# nisetoro_wsc_adapter_v2.net
KiCad netlist of a schematic drawn in EAGLE
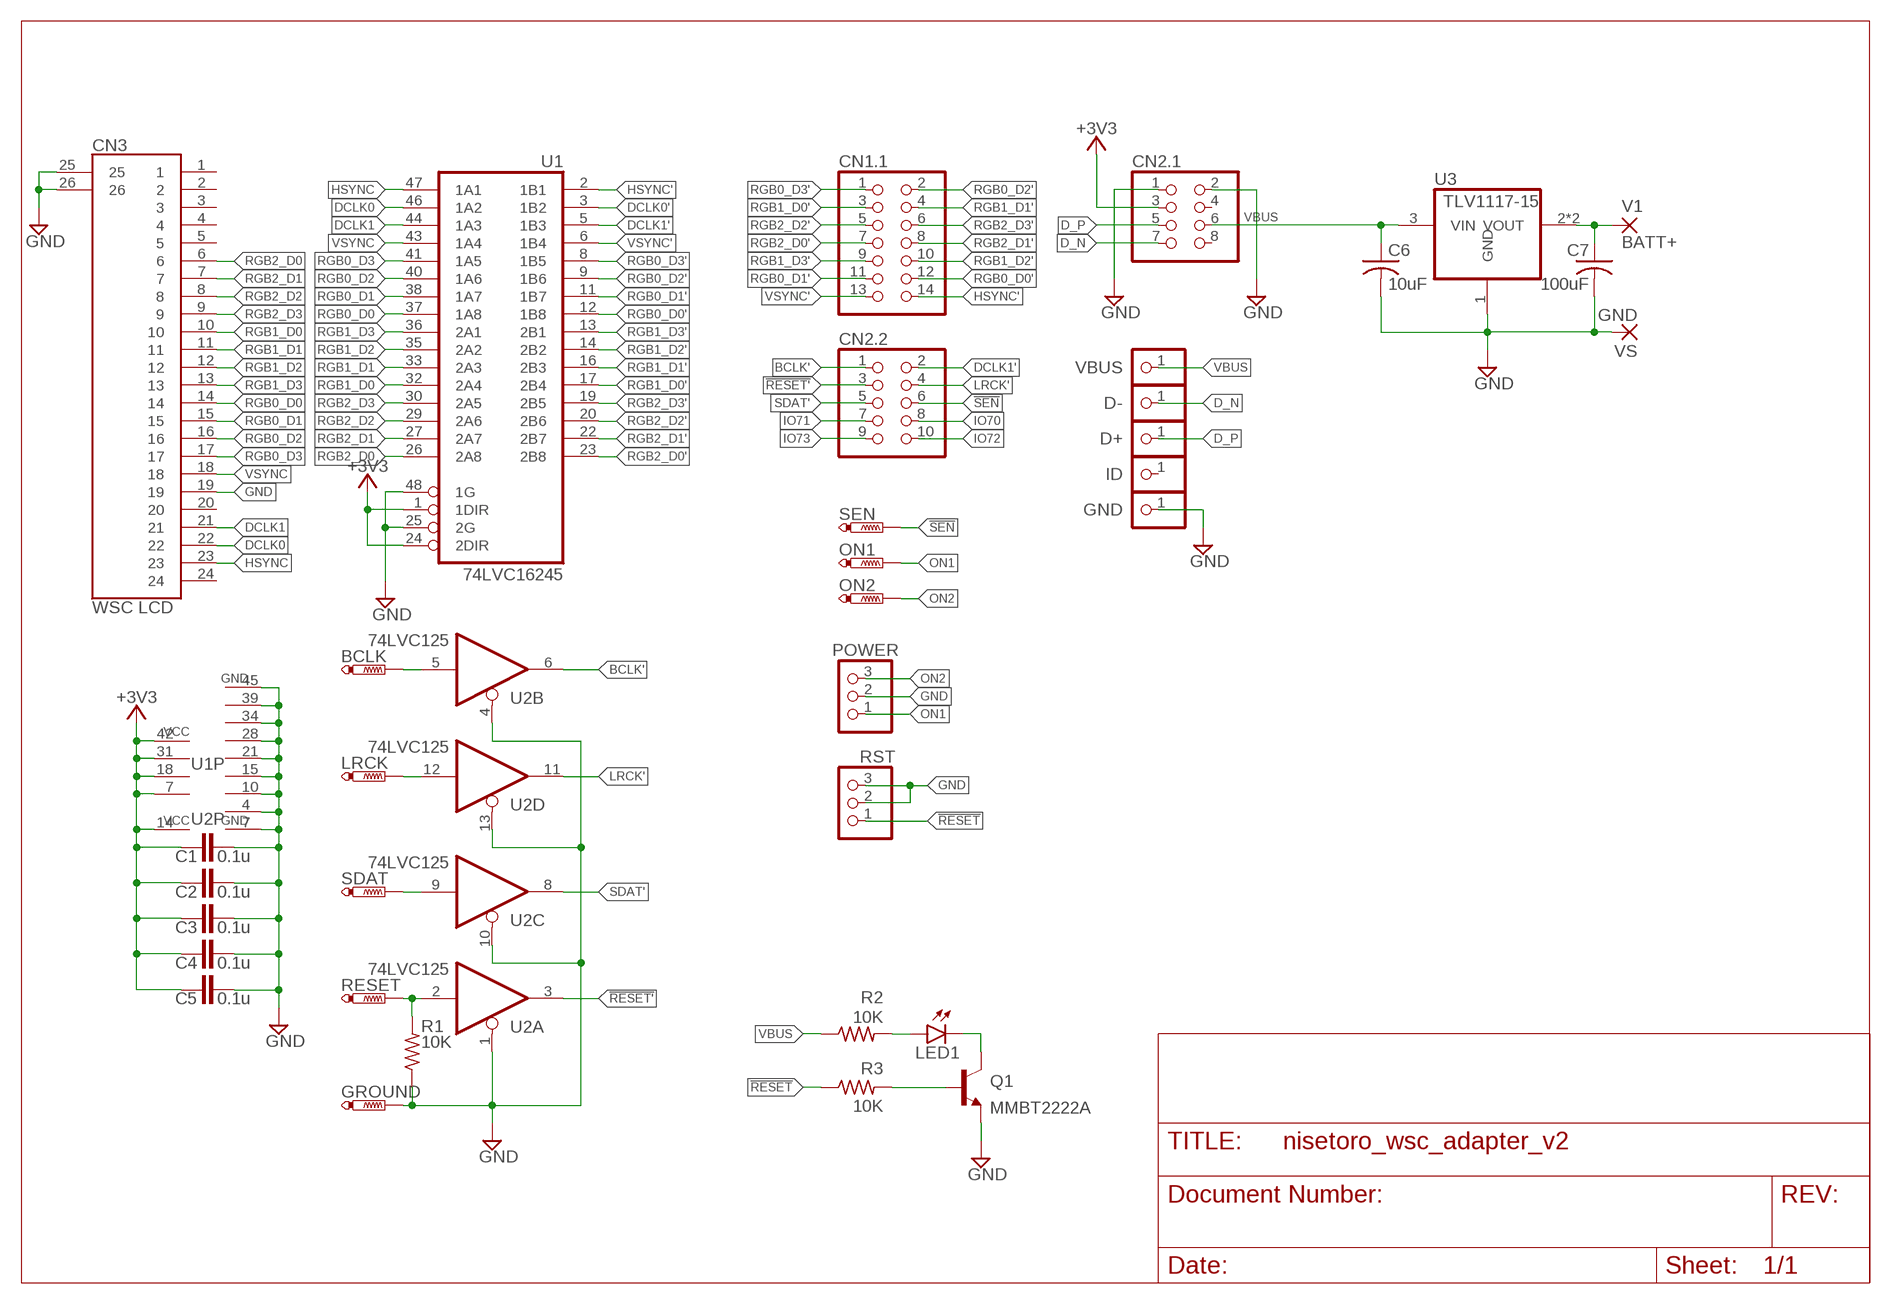
[diagram p0: schematic, sheet 1]

(export (version "E")
  (design (tool "Eeschema 10.0.6"))
  (components
    (comp (ref "BCLK")
      (value "PTR1B1,27")
      (footprint "eagle-import:B1,27")
      (libsource (lib "eagle-import") (part "PTR1B1,27"))
    )
    (comp (ref "C1")
      (value "0.1u")
      (footprint "eagle-import:C0603")
      (libsource (lib "eagle-import") (part "C-EUC0603"))
    )
    (comp (ref "C2")
      (value "0.1u")
      (footprint "eagle-import:C0603")
      (libsource (lib "eagle-import") (part "C-EUC0603"))
    )
    (comp (ref "C3")
      (value "0.1u")
      (footprint "eagle-import:C0603")
      (libsource (lib "eagle-import") (part "C-EUC0603"))
    )
    (comp (ref "C4")
      (value "0.1u")
      (footprint "eagle-import:C0603")
      (libsource (lib "eagle-import") (part "C-EUC0603"))
    )
    (comp (ref "C5")
      (value "0.1u")
      (footprint "eagle-import:C0603")
      (libsource (lib "eagle-import") (part "C-EUC0603"))
    )
    (comp (ref "C6")
      (value "10uF")
      (footprint "eagle-import:C1210")
      (libsource (lib "eagle-import") (part "C-USC1210"))
    )
    (comp (ref "C7")
      (value "100uF")
      (footprint "eagle-import:C1210")
      (libsource (lib "eagle-import") (part "C-USC1210"))
    )
    (comp (ref "CN1.1")
      (value "PINHD-2X7")
      (footprint "eagle-import:2X07")
      (libsource (lib "eagle-import") (part "PINHD-2X7"))
    )
    (comp (ref "CN2.1")
      (value "PINHD-2X4")
      (footprint "eagle-import:2X04")
      (libsource (lib "eagle-import") (part "PINHD-2X4"))
    )
    (comp (ref "CN2.2")
      (value "PINHD-2X5")
      (footprint "eagle-import:2X05")
      (libsource (lib "eagle-import") (part "PINHD-2X5"))
    )
    (comp (ref "CN3")
      (value "WSC LCD")
      (footprint "eagle-import:68712414022_R")
      (libsource (lib "eagle-import") (part "68712414022/R"))
    )
    (comp (ref "D+")
      (value "PINHD-1X1")
      (footprint "eagle-import:1X01")
      (libsource (lib "eagle-import") (part "PINHD-1X1"))
    )
    (comp (ref "D-")
      (value "PINHD-1X1")
      (footprint "eagle-import:1X01")
      (libsource (lib "eagle-import") (part "PINHD-1X1"))
    )
    (comp (ref "GND")
      (value "PINHD-1X1")
      (footprint "eagle-import:1X01")
      (libsource (lib "eagle-import") (part "PINHD-1X1"))
    )
    (comp (ref "GROUND")
      (value "PTR1B1,27")
      (footprint "eagle-import:B1,27")
      (libsource (lib "eagle-import") (part "PTR1B1,27"))
    )
    (comp (ref "ID")
      (value "PINHD-1X1")
      (footprint "eagle-import:1X01")
      (libsource (lib "eagle-import") (part "PINHD-1X1"))
    )
    (comp (ref "LED1")
      (value "LEDSML0603")
      (footprint "eagle-import:SML0603")
      (libsource (lib "eagle-import") (part "LEDSML0603"))
    )
    (comp (ref "LRCK")
      (value "PTR1B1,27")
      (footprint "eagle-import:B1,27")
      (libsource (lib "eagle-import") (part "PTR1B1,27"))
    )
    (comp (ref "ON1")
      (value "PTR1B1,27")
      (footprint "eagle-import:B1,27")
      (libsource (lib "eagle-import") (part "PTR1B1,27"))
    )
    (comp (ref "ON2")
      (value "PTR1B1,27")
      (footprint "eagle-import:B1,27")
      (libsource (lib "eagle-import") (part "PTR1B1,27"))
    )
    (comp (ref "POWER")
      (value "PINHD-1X3/ROUND")
      (footprint "eagle-import:1X03_ROUND")
      (libsource (lib "eagle-import") (part "PINHD-1X3/ROUND"))
    )
    (comp (ref "Q1")
      (value "MMBT2222A")
      (footprint "eagle-import:SOT23-BEC")
      (libsource (lib "eagle-import") (part "2N2222SOT23"))
    )
    (comp (ref "R1")
      (value "10K")
      (footprint "eagle-import:R0603")
      (libsource (lib "eagle-import") (part "R-US_R0603"))
    )
    (comp (ref "R2")
      (value "10K")
      (footprint "eagle-import:R0603")
      (libsource (lib "eagle-import") (part "R-US_R0603"))
    )
    (comp (ref "R3")
      (value "10K")
      (footprint "eagle-import:R0603")
      (libsource (lib "eagle-import") (part "R-US_R0603"))
    )
    (comp (ref "RESET")
      (value "PTR1B1,27")
      (footprint "eagle-import:B1,27")
      (libsource (lib "eagle-import") (part "PTR1B1,27"))
    )
    (comp (ref "RST")
      (value "PINHD-1X3/ROUND")
      (footprint "eagle-import:1X03_ROUND")
      (libsource (lib "eagle-import") (part "PINHD-1X3/ROUND"))
    )
    (comp (ref "SDAT")
      (value "PTR1B1,27")
      (footprint "eagle-import:B1,27")
      (libsource (lib "eagle-import") (part "PTR1B1,27"))
    )
    (comp (ref "SEN")
      (value "PTR1B1,27")
      (footprint "eagle-import:B1,27")
      (libsource (lib "eagle-import") (part "PTR1B1,27"))
    )
    (comp (ref "U1")
      (value "74LVC16245")
      (footprint "eagle-import:TSSOP48")
      (libsource (lib "eagle-import") (part "74AC16245DGG"))
    )
    (comp (ref "U2")
      (value "74LVC125")
      (footprint "eagle-import:TSSOP14")
      (libsource (lib "eagle-import") (part "74125PWABT"))
    )
    (comp (ref "U3")
      (value "TLV1117-15")
      (footprint "eagle-import:SOT223")
      (fields (field (name "MPN") "REG1117"))
      (libsource (lib "eagle-import") (part "REG1117"))
    )
    (comp (ref "V1")
      (value "BATT+")
      (footprint "eagle-import:SMD2,54-5,08")
      (libsource (lib "eagle-import") (part "WIREPADSMD2,54-5,08"))
    )
    (comp (ref "VBUS")
      (value "PINHD-1X1")
      (footprint "eagle-import:1X01")
      (libsource (lib "eagle-import") (part "PINHD-1X1"))
    )
    (comp (ref "VS")
      (value "GND")
      (footprint "eagle-import:SMD2,54-5,08")
      (libsource (lib "eagle-import") (part "WIREPADSMD2,54-5,08"))
    )
  )
  (nets
    (net (code "1") (name "+3V3") (class "Default")
      (node (ref "C1") (pin "1") (pinfunction "1_1") (pintype "passive"))
      (node (ref "C2") (pin "1") (pinfunction "1_1") (pintype "passive"))
      (node (ref "C3") (pin "1") (pinfunction "1_1") (pintype "passive"))
      (node (ref "C4") (pin "1") (pinfunction "1_1") (pintype "passive"))
      (node (ref "C5") (pin "1") (pinfunction "1_1") (pintype "passive"))
      (node (ref "CN2.1") (pin "3") (pinfunction "3_3") (pintype "passive"))
      (node (ref "U1") (pin "1") (pinfunction "1DIR_1") (pintype "input"))
      (node (ref "U1") (pin "18") (pinfunction "VCC_18") (pintype "power_in"))
      (node (ref "U1") (pin "24") (pinfunction "2DIR_24") (pintype "input"))
      (node (ref "U1") (pin "31") (pinfunction "VCC_31") (pintype "power_in"))
      (node (ref "U1") (pin "42") (pinfunction "VCC_42") (pintype "power_in"))
      (node (ref "U1") (pin "7") (pinfunction "VCC_7") (pintype "power_in"))
      (node (ref "U2") (pin "14") (pinfunction "VCC_14") (pintype "power_in"))
    )
    (net (code "2") (name "/~{RESET'}") (class "Default")
      (node (ref "CN2.2") (pin "3") (pinfunction "3_3") (pintype "passive"))
      (node (ref "U2") (pin "3") (pinfunction "O_3") (pintype "tri_state"))
    )
    (net (code "3") (name "/~{RESET}") (class "Default")
      (node (ref "R1") (pin "2") (pinfunction "2_2") (pintype "passive"))
      (node (ref "R3") (pin "1") (pinfunction "1_1") (pintype "passive"))
      (node (ref "RESET") (pin "TP") (pinfunction "TP_TP") (pintype "input"))
      (node (ref "RST") (pin "1") (pinfunction "1_1") (pintype "passive"))
      (node (ref "U2") (pin "2") (pinfunction "I_2") (pintype "input"))
    )
    (net (code "4") (name "/~{SEN}") (class "Default")
      (node (ref "CN2.2") (pin "6") (pinfunction "6_6") (pintype "passive"))
      (node (ref "SEN") (pin "TP") (pinfunction "TP_TP") (pintype "input"))
    )
    (net (code "5") (name "BCLK'") (class "Default")
      (node (ref "CN2.2") (pin "1") (pinfunction "1_1") (pintype "passive"))
      (node (ref "U2") (pin "6") (pinfunction "O_6") (pintype "tri_state"))
    )
    (net (code "6") (name "DCLK0") (class "Default")
      (node (ref "CN3") (pin "22") (pinfunction "22_22") (pintype "bidirectional"))
      (node (ref "U1") (pin "46") (pinfunction "1A2_46") (pintype "bidirectional"))
    )
    (net (code "7") (name "DCLK0'") (class "Default")
      (node (ref "U1") (pin "3") (pinfunction "1B2_3") (pintype "bidirectional"))
    )
    (net (code "8") (name "DCLK1") (class "Default")
      (node (ref "CN3") (pin "21") (pinfunction "21_21") (pintype "bidirectional"))
      (node (ref "U1") (pin "44") (pinfunction "1A3_44") (pintype "bidirectional"))
    )
    (net (code "9") (name "DCLK1'") (class "Default")
      (node (ref "CN2.2") (pin "2") (pinfunction "2_2") (pintype "passive"))
      (node (ref "U1") (pin "5") (pinfunction "1B3_5") (pintype "bidirectional"))
    )
    (net (code "10") (name "D_N") (class "Default")
      (node (ref "CN2.1") (pin "7") (pinfunction "7_7") (pintype "passive"))
      (node (ref "D-") (pin "1") (pinfunction "1_1") (pintype "passive"))
    )
    (net (code "11") (name "D_P") (class "Default")
      (node (ref "CN2.1") (pin "5") (pinfunction "5_5") (pintype "passive"))
      (node (ref "D+") (pin "1") (pinfunction "1_1") (pintype "passive"))
    )
    (net (code "12") (name "GND") (class "Default")
      (node (ref "C1") (pin "2") (pinfunction "2_2") (pintype "passive"))
      (node (ref "C2") (pin "2") (pinfunction "2_2") (pintype "passive"))
      (node (ref "C3") (pin "2") (pinfunction "2_2") (pintype "passive"))
      (node (ref "C4") (pin "2") (pinfunction "2_2") (pintype "passive"))
      (node (ref "C5") (pin "2") (pinfunction "2_2") (pintype "passive"))
      (node (ref "C6") (pin "2") (pinfunction "2_2") (pintype "passive"))
      (node (ref "C7") (pin "2") (pinfunction "2_2") (pintype "passive"))
      (node (ref "CN2.1") (pin "1") (pinfunction "1_1") (pintype "passive"))
      (node (ref "CN2.1") (pin "2") (pinfunction "2_2") (pintype "passive"))
      (node (ref "CN3") (pin "19") (pinfunction "19_19") (pintype "bidirectional"))
      (node (ref "CN3") (pin "25") (pinfunction "25_25") (pintype "bidirectional"))
      (node (ref "CN3") (pin "26") (pinfunction "26_26") (pintype "bidirectional"))
      (node (ref "GND") (pin "1") (pinfunction "1_1") (pintype "passive"))
      (node (ref "GROUND") (pin "TP") (pinfunction "TP_TP") (pintype "input"))
      (node (ref "POWER") (pin "2") (pinfunction "2_2") (pintype "passive"))
      (node (ref "Q1") (pin "E") (pinfunction "E_E") (pintype "passive"))
      (node (ref "R1") (pin "1") (pinfunction "1_1") (pintype "passive"))
      (node (ref "RST") (pin "2") (pinfunction "2_2") (pintype "passive"))
      (node (ref "RST") (pin "3") (pinfunction "3_3") (pintype "passive"))
      (node (ref "U1") (pin "10") (pinfunction "GND_10") (pintype "power_in"))
      (node (ref "U1") (pin "15") (pinfunction "GND_15") (pintype "power_in"))
      (node (ref "U1") (pin "21") (pinfunction "GND_21") (pintype "power_in"))
      (node (ref "U1") (pin "25") (pinfunction "2G_25") (pintype "input"))
      (node (ref "U1") (pin "28") (pinfunction "GND_28") (pintype "power_in"))
      (node (ref "U1") (pin "34") (pinfunction "GND_34") (pintype "power_in"))
      (node (ref "U1") (pin "39") (pinfunction "GND_39") (pintype "power_in"))
      (node (ref "U1") (pin "4") (pinfunction "GND_4") (pintype "power_in"))
      (node (ref "U1") (pin "45") (pinfunction "GND_45") (pintype "power_in"))
      (node (ref "U1") (pin "48") (pinfunction "1G_48") (pintype "input"))
      (node (ref "U2") (pin "1") (pinfunction "OE_1") (pintype "input"))
      (node (ref "U2") (pin "10") (pinfunction "OE_10") (pintype "input"))
      (node (ref "U2") (pin "13") (pinfunction "OE_13") (pintype "input"))
      (node (ref "U2") (pin "4") (pinfunction "OE_4") (pintype "input"))
      (node (ref "U2") (pin "7") (pinfunction "GND_7") (pintype "power_in"))
      (node (ref "U3") (pin "1") (pinfunction "GND_1") (pintype "power_in"))
      (node (ref "VS") (pin "1") (pinfunction "P_1") (pintype "passive"))
    )
    (net (code "13") (name "HSYNC") (class "Default")
      (node (ref "CN3") (pin "23") (pinfunction "23_23") (pintype "bidirectional"))
      (node (ref "U1") (pin "47") (pinfunction "1A1_47") (pintype "bidirectional"))
    )
    (net (code "14") (name "HSYNC'") (class "Default")
      (node (ref "CN1.1") (pin "14") (pinfunction "14_14") (pintype "passive"))
      (node (ref "U1") (pin "2") (pinfunction "1B1_2") (pintype "bidirectional"))
    )
    (net (code "15") (name "IO70") (class "Default")
      (node (ref "CN2.2") (pin "8") (pinfunction "8_8") (pintype "passive"))
    )
    (net (code "16") (name "IO71") (class "Default")
      (node (ref "CN2.2") (pin "7") (pinfunction "7_7") (pintype "passive"))
    )
    (net (code "17") (name "IO72") (class "Default")
      (node (ref "CN2.2") (pin "10") (pinfunction "10_10") (pintype "passive"))
    )
    (net (code "18") (name "IO73") (class "Default")
      (node (ref "CN2.2") (pin "9") (pinfunction "9_9") (pintype "passive"))
    )
    (net (code "19") (name "LRCK'") (class "Default")
      (node (ref "CN2.2") (pin "4") (pinfunction "4_4") (pintype "passive"))
      (node (ref "U2") (pin "11") (pinfunction "O_11") (pintype "tri_state"))
    )
    (net (code "20") (name "Net-(LED1-PadA)") (class "Default")
      (node (ref "LED1") (pin "A") (pinfunction "A_A") (pintype "passive"))
      (node (ref "R2") (pin "2") (pinfunction "2_2") (pintype "passive"))
    )
    (net (code "21") (name "Net-(LED1-PadC)") (class "Default")
      (node (ref "LED1") (pin "C") (pinfunction "C_C") (pintype "passive"))
      (node (ref "Q1") (pin "C") (pinfunction "C_C") (pintype "passive"))
    )
    (net (code "22") (name "Net-(Q1-PadB)") (class "Default")
      (node (ref "Q1") (pin "B") (pinfunction "B_B") (pintype "passive"))
      (node (ref "R3") (pin "2") (pinfunction "2_2") (pintype "passive"))
    )
    (net (code "23") (name "Net-(U2B-I)") (class "Default")
      (node (ref "BCLK") (pin "TP") (pinfunction "TP_TP") (pintype "input"))
      (node (ref "U2") (pin "5") (pinfunction "I_5") (pintype "input"))
    )
    (net (code "24") (name "Net-(U2C-I)") (class "Default")
      (node (ref "SDAT") (pin "TP") (pinfunction "TP_TP") (pintype "input"))
      (node (ref "U2") (pin "9") (pinfunction "I_9") (pintype "input"))
    )
    (net (code "25") (name "Net-(U2D-I)") (class "Default")
      (node (ref "LRCK") (pin "TP") (pinfunction "TP_TP") (pintype "input"))
      (node (ref "U2") (pin "12") (pinfunction "I_12") (pintype "input"))
    )
    (net (code "26") (name "Net-(V1-P)") (class "Default")
      (node (ref "C7") (pin "1") (pinfunction "1_1") (pintype "passive"))
      (node (ref "U3") (pin "2") (pinfunction "VOUT_2") (pintype "output"))
      (node (ref "U3") (pin "4") (pinfunction "VOUT_4") (pintype "output"))
      (node (ref "V1") (pin "1") (pinfunction "P_1") (pintype "passive"))
    )
    (net (code "27") (name "ON1") (class "Default")
      (node (ref "ON1") (pin "TP") (pinfunction "TP_TP") (pintype "input"))
      (node (ref "POWER") (pin "1") (pinfunction "1_1") (pintype "passive"))
    )
    (net (code "28") (name "ON2") (class "Default")
      (node (ref "ON2") (pin "TP") (pinfunction "TP_TP") (pintype "input"))
      (node (ref "POWER") (pin "3") (pinfunction "3_3") (pintype "passive"))
    )
    (net (code "29") (name "RGB0_D0") (class "Default")
      (node (ref "CN3") (pin "14") (pinfunction "14_14") (pintype "bidirectional"))
      (node (ref "U1") (pin "37") (pinfunction "1A8_37") (pintype "bidirectional"))
    )
    (net (code "30") (name "RGB0_D0'") (class "Default")
      (node (ref "CN1.1") (pin "12") (pinfunction "12_12") (pintype "passive"))
      (node (ref "U1") (pin "12") (pinfunction "1B8_12") (pintype "bidirectional"))
    )
    (net (code "31") (name "RGB0_D1") (class "Default")
      (node (ref "CN3") (pin "15") (pinfunction "15_15") (pintype "bidirectional"))
      (node (ref "U1") (pin "38") (pinfunction "1A7_38") (pintype "bidirectional"))
    )
    (net (code "32") (name "RGB0_D1'") (class "Default")
      (node (ref "CN1.1") (pin "11") (pinfunction "11_11") (pintype "passive"))
      (node (ref "U1") (pin "11") (pinfunction "1B7_11") (pintype "bidirectional"))
    )
    (net (code "33") (name "RGB0_D2") (class "Default")
      (node (ref "CN3") (pin "16") (pinfunction "16_16") (pintype "bidirectional"))
      (node (ref "U1") (pin "40") (pinfunction "1A6_40") (pintype "bidirectional"))
    )
    (net (code "34") (name "RGB0_D2'") (class "Default")
      (node (ref "CN1.1") (pin "2") (pinfunction "2_2") (pintype "passive"))
      (node (ref "U1") (pin "9") (pinfunction "1B6_9") (pintype "bidirectional"))
    )
    (net (code "35") (name "RGB0_D3") (class "Default")
      (node (ref "CN3") (pin "17") (pinfunction "17_17") (pintype "bidirectional"))
      (node (ref "U1") (pin "41") (pinfunction "1A5_41") (pintype "bidirectional"))
    )
    (net (code "36") (name "RGB0_D3'") (class "Default")
      (node (ref "CN1.1") (pin "1") (pinfunction "1_1") (pintype "passive"))
      (node (ref "U1") (pin "8") (pinfunction "1B5_8") (pintype "bidirectional"))
    )
    (net (code "37") (name "RGB1_D0") (class "Default")
      (node (ref "CN3") (pin "10") (pinfunction "10_10") (pintype "bidirectional"))
      (node (ref "U1") (pin "32") (pinfunction "2A4_32") (pintype "bidirectional"))
    )
    (net (code "38") (name "RGB1_D0'") (class "Default")
      (node (ref "CN1.1") (pin "3") (pinfunction "3_3") (pintype "passive"))
      (node (ref "U1") (pin "17") (pinfunction "2B4_17") (pintype "bidirectional"))
    )
    (net (code "39") (name "RGB1_D1") (class "Default")
      (node (ref "CN3") (pin "11") (pinfunction "11_11") (pintype "bidirectional"))
      (node (ref "U1") (pin "33") (pinfunction "2A3_33") (pintype "bidirectional"))
    )
    (net (code "40") (name "RGB1_D1'") (class "Default")
      (node (ref "CN1.1") (pin "4") (pinfunction "4_4") (pintype "passive"))
      (node (ref "U1") (pin "16") (pinfunction "2B3_16") (pintype "bidirectional"))
    )
    (net (code "41") (name "RGB1_D2") (class "Default")
      (node (ref "CN3") (pin "12") (pinfunction "12_12") (pintype "bidirectional"))
      (node (ref "U1") (pin "35") (pinfunction "2A2_35") (pintype "bidirectional"))
    )
    (net (code "42") (name "RGB1_D2'") (class "Default")
      (node (ref "CN1.1") (pin "10") (pinfunction "10_10") (pintype "passive"))
      (node (ref "U1") (pin "14") (pinfunction "2B2_14") (pintype "bidirectional"))
    )
    (net (code "43") (name "RGB1_D3") (class "Default")
      (node (ref "CN3") (pin "13") (pinfunction "13_13") (pintype "bidirectional"))
      (node (ref "U1") (pin "36") (pinfunction "2A1_36") (pintype "bidirectional"))
    )
    (net (code "44") (name "RGB1_D3'") (class "Default")
      (node (ref "CN1.1") (pin "9") (pinfunction "9_9") (pintype "passive"))
      (node (ref "U1") (pin "13") (pinfunction "2B1_13") (pintype "bidirectional"))
    )
    (net (code "45") (name "RGB2_D0") (class "Default")
      (node (ref "CN3") (pin "6") (pinfunction "6_6") (pintype "bidirectional"))
      (node (ref "U1") (pin "26") (pinfunction "2A8_26") (pintype "bidirectional"))
    )
    (net (code "46") (name "RGB2_D0'") (class "Default")
      (node (ref "CN1.1") (pin "7") (pinfunction "7_7") (pintype "passive"))
      (node (ref "U1") (pin "23") (pinfunction "2B8_23") (pintype "bidirectional"))
    )
    (net (code "47") (name "RGB2_D1") (class "Default")
      (node (ref "CN3") (pin "7") (pinfunction "7_7") (pintype "bidirectional"))
      (node (ref "U1") (pin "27") (pinfunction "2A7_27") (pintype "bidirectional"))
    )
    (net (code "48") (name "RGB2_D1'") (class "Default")
      (node (ref "CN1.1") (pin "8") (pinfunction "8_8") (pintype "passive"))
      (node (ref "U1") (pin "22") (pinfunction "2B7_22") (pintype "bidirectional"))
    )
    (net (code "49") (name "RGB2_D2") (class "Default")
      (node (ref "CN3") (pin "8") (pinfunction "8_8") (pintype "bidirectional"))
      (node (ref "U1") (pin "29") (pinfunction "2A6_29") (pintype "bidirectional"))
    )
    (net (code "50") (name "RGB2_D2'") (class "Default")
      (node (ref "CN1.1") (pin "5") (pinfunction "5_5") (pintype "passive"))
      (node (ref "U1") (pin "20") (pinfunction "2B6_20") (pintype "bidirectional"))
    )
    (net (code "51") (name "RGB2_D3") (class "Default")
      (node (ref "CN3") (pin "9") (pinfunction "9_9") (pintype "bidirectional"))
      (node (ref "U1") (pin "30") (pinfunction "2A5_30") (pintype "bidirectional"))
    )
    (net (code "52") (name "RGB2_D3'") (class "Default")
      (node (ref "CN1.1") (pin "6") (pinfunction "6_6") (pintype "passive"))
      (node (ref "U1") (pin "19") (pinfunction "2B5_19") (pintype "bidirectional"))
    )
    (net (code "53") (name "SDAT'") (class "Default")
      (node (ref "CN2.2") (pin "5") (pinfunction "5_5") (pintype "passive"))
      (node (ref "U2") (pin "8") (pinfunction "O_8") (pintype "tri_state"))
    )
    (net (code "54") (name "VBUS") (class "Default")
      (node (ref "C6") (pin "1") (pinfunction "1_1") (pintype "passive"))
      (node (ref "CN2.1") (pin "6") (pinfunction "6_6") (pintype "passive"))
      (node (ref "R2") (pin "1") (pinfunction "1_1") (pintype "passive"))
      (node (ref "U3") (pin "3") (pinfunction "VIN_3") (pintype "input"))
      (node (ref "VBUS") (pin "1") (pinfunction "1_1") (pintype "passive"))
    )
    (net (code "55") (name "VSYNC") (class "Default")
      (node (ref "CN3") (pin "18") (pinfunction "18_18") (pintype "bidirectional"))
      (node (ref "U1") (pin "43") (pinfunction "1A4_43") (pintype "bidirectional"))
    )
    (net (code "56") (name "VSYNC'") (class "Default")
      (node (ref "CN1.1") (pin "13") (pinfunction "13_13") (pintype "passive"))
      (node (ref "U1") (pin "6") (pinfunction "1B4_6") (pintype "bidirectional"))
    )
    (net (code "57") (name "unconnected-(CN2.1-Pad4)") (class "Default")
      (node (ref "CN2.1") (pin "4") (pinfunction "4_4") (pintype "passive"))
    )
    (net (code "58") (name "unconnected-(CN2.1-Pad8)") (class "Default")
      (node (ref "CN2.1") (pin "8") (pinfunction "8_8") (pintype "passive"))
    )
    (net (code "59") (name "unconnected-(CN3-Pad1)") (class "Default")
      (node (ref "CN3") (pin "1") (pinfunction "1_1") (pintype "bidirectional"))
    )
    (net (code "60") (name "unconnected-(CN3-Pad2)") (class "Default")
      (node (ref "CN3") (pin "2") (pinfunction "2_2") (pintype "bidirectional"))
    )
    (net (code "61") (name "unconnected-(CN3-Pad3)") (class "Default")
      (node (ref "CN3") (pin "3") (pinfunction "3_3") (pintype "bidirectional"))
    )
    (net (code "62") (name "unconnected-(CN3-Pad4)") (class "Default")
      (node (ref "CN3") (pin "4") (pinfunction "4_4") (pintype "bidirectional"))
    )
    (net (code "63") (name "unconnected-(CN3-Pad5)") (class "Default")
      (node (ref "CN3") (pin "5") (pinfunction "5_5") (pintype "bidirectional"))
    )
    (net (code "64") (name "unconnected-(CN3-Pad20)") (class "Default")
      (node (ref "CN3") (pin "20") (pinfunction "20_20") (pintype "bidirectional"))
    )
    (net (code "65") (name "unconnected-(CN3-Pad24)") (class "Default")
      (node (ref "CN3") (pin "24") (pinfunction "24_24") (pintype "bidirectional"))
    )
    (net (code "66") (name "unconnected-(ID-Pad1)") (class "Default")
      (node (ref "ID") (pin "1") (pinfunction "1_1") (pintype "passive"))
    )
  )
)
